# 4_1_frontend.net
KiCad netlist of a schematic drawn in Altium Designer
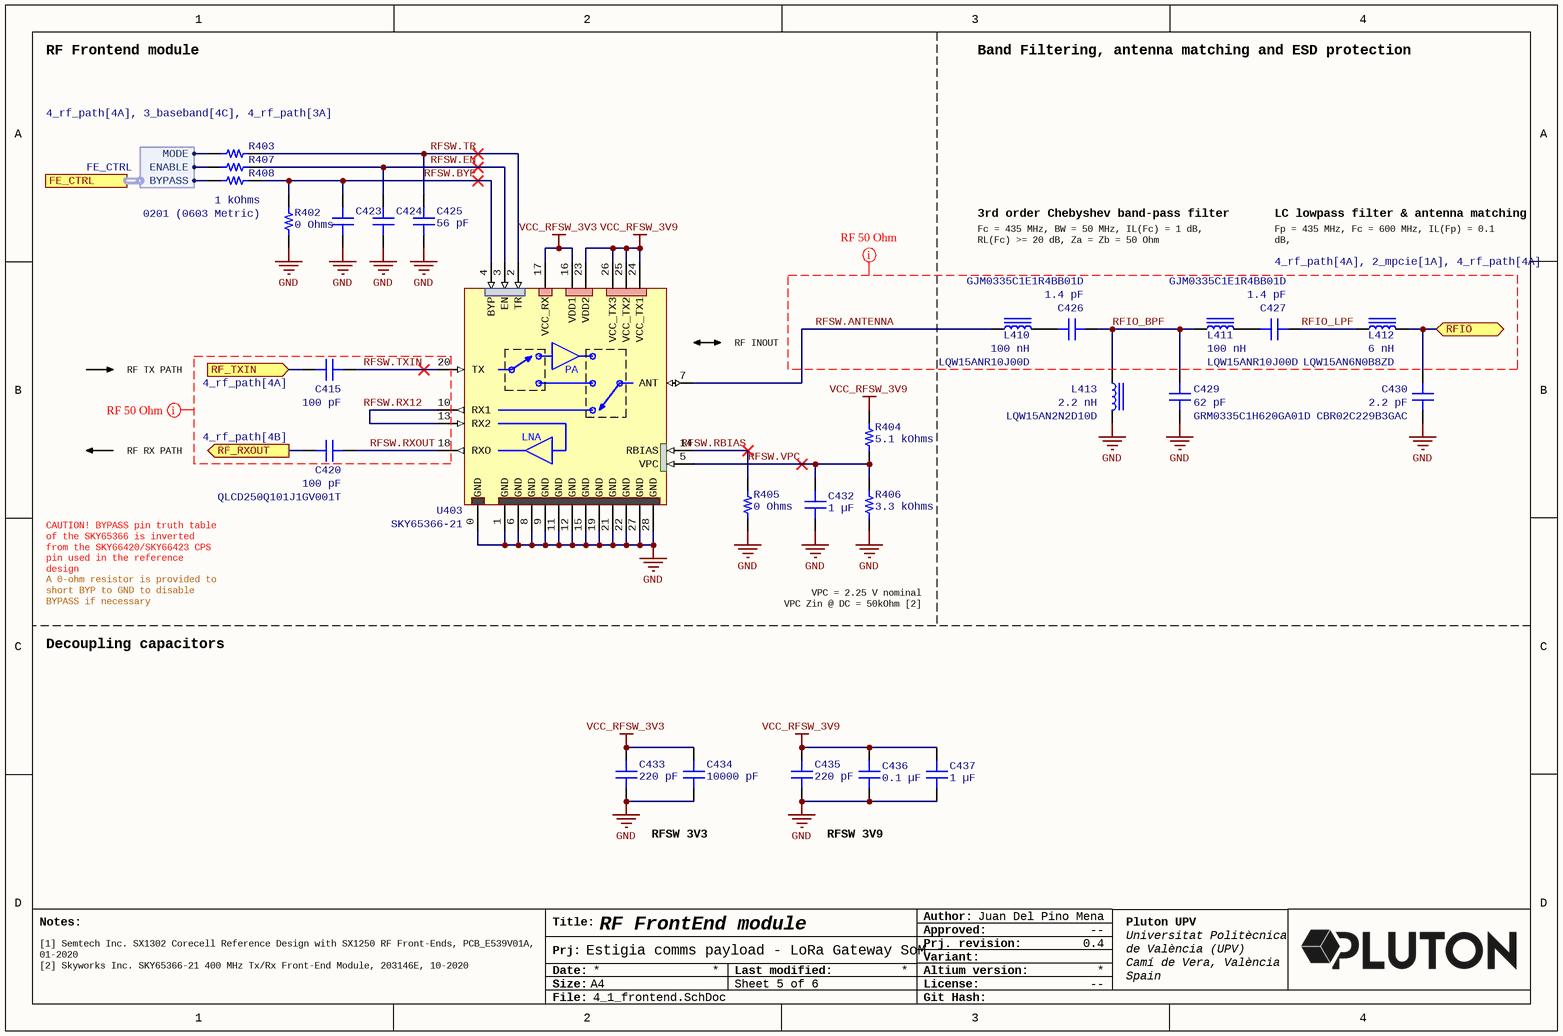
[diagram p0: 4_1_frontend.SchDoc]

(export (version "E")
  (design (tool "Eeschema 10.0.6"))
  (components
    (comp (ref "C415")
      (value "100 pF")
      (footprint "CAP 0201_0603 RF")
      (description "CAP CER 100PF 25V C0G/NP0 0201")
      (fields
        (field (name "PART NUMBER") "QLCD250Q101J1GV001T")
        (field (name "CAPACITANCE") "100 pF")
        (field (name "MANUFACTURER") "Johanson Technology Inc.")
        (field (name "TOLERANCE") "±5%")
      )
      (libsource (lib "Celestial Altium Library - altium_library") (part "Capacitor"))
    )
    (comp (ref "C420")
      (value "100 pF")
      (footprint "CAP 0201_0603 RF")
      (description "CAP CER 100PF 25V C0G/NP0 0201")
      (fields
        (field (name "PART NUMBER") "QLCD250Q101J1GV001T")
        (field (name "CAPACITANCE") "100 pF")
        (field (name "MANUFACTURER") "Johanson Technology Inc.")
      )
      (libsource (lib "Celestial Altium Library - altium_library") (part "Capacitor"))
    )
    (comp (ref "C423")
      (value "56 pF")
      (footprint "CAP 0201_0603")
      (description "CAP CER 56PF 50V C0G/NP0 0201")
      (fields
        (field (name "PART NUMBER") "GRM0335C1H560GA01D")
        (field (name "MANUFACTURER") "Murata Electronics")
      )
      (libsource (lib "Celestial Altium Library - altium_library") (part "Capacitor"))
    )
    (comp (ref "C424")
      (value "56 pF")
      (footprint "CAP 0201_0603")
      (description "CAP CER 56PF 50V C0G/NP0 0201")
      (fields
        (field (name "PART NUMBER") "GRM0335C1H560GA01D")
        (field (name "MANUFACTURER") "Murata Electronics")
      )
      (libsource (lib "Celestial Altium Library - altium_library") (part "Capacitor"))
    )
    (comp (ref "C425")
      (value "56 pF")
      (footprint "CAP 0201_0603")
      (description "CAP CER 56PF 50V C0G/NP0 0201")
      (fields
        (field (name "PART NUMBER") "GRM0335C1H560GA01D")
        (field (name "MANUFACTURER") "Murata Electronics")
      )
      (libsource (lib "Celestial Altium Library - altium_library") (part "Capacitor"))
    )
    (comp (ref "C426")
      (value "1.4 pF")
      (footprint "CAP 0201_0603 RF")
      (description "CAP CER 1.4PF 25V C0G/NP0 0201")
      (fields
        (field (name "PART NUMBER") "GJM0335C1E1R4BB01D")
        (field (name "MANUFACTURER") "Murata Electronics")
        (field (name "TOLERANCE") "±0.1pF")
      )
      (libsource (lib "Celestial Altium Library - altium_library") (part "Capacitor"))
    )
    (comp (ref "C427")
      (value "1.4 pF")
      (footprint "CAP 0201_0603 RF")
      (description "CAP CER 1.4PF 25V C0G/NP0 0201")
      (fields
        (field (name "PART NUMBER") "GJM0335C1E1R4BB01D")
        (field (name "MANUFACTURER") "Murata Electronics")
        (field (name "TOLERANCE") "±0.1pF")
      )
      (libsource (lib "Celestial Altium Library - altium_library") (part "Capacitor"))
    )
    (comp (ref "C429")
      (value "62 pF")
      (footprint "CAP 0201_0603")
      (description "CAP CER 62PF 50V C0G/NP0 0201")
      (fields
        (field (name "PART NUMBER") "GRM0335C1H620GA01D")
        (field (name "MANUFACTURER") "Murata Electronics")
        (field (name "TOLERANCE") "±2%")
      )
      (libsource (lib "Celestial Altium Library - altium_library") (part "Capacitor"))
    )
    (comp (ref "C430")
      (value "2.2 pF")
      (footprint "CAP 0201_0603 RF")
      (description "CAP CER 2.2PF 25V C0G/NP0 0201")
      (fields
        (field (name "PART NUMBER") "CBR02C229B3GAC")
        (field (name "MANUFACTURER") "KEMET")
        (field (name "TOLERANCE") "±0.1pF")
      )
      (libsource (lib "Celestial Altium Library - altium_library") (part "Capacitor"))
    )
    (comp (ref "C432")
      (value "1 µF")
      (footprint "CAP 0402_1005")
      (description "CAP CER 1UF 16V X5R 0402")
      (fields
        (field (name "PART NUMBER") "CL05A105KO5NNNC")
        (field (name "MANUFACTURER") "Samsung Electro-Mechanics")
      )
      (libsource (lib "Celestial Altium Library - altium_library") (part "Capacitor"))
    )
    (comp (ref "C433")
      (value "220 pF")
      (footprint "CAP 0201_0603")
      (description "CAP CER 220PF 50V C0G/NP0 0201")
      (fields
        (field (name "PART NUMBER") "GRM0335C1H221JA01D")
        (field (name "MANUFACTURER") "Murata Electronics")
      )
      (libsource (lib "Celestial Altium Library - altium_library") (part "Capacitor"))
    )
    (comp (ref "C434")
      (value "10000 pF")
      (footprint "CAP 0402_1005")
      (description "CAP CER 10000PF 25V C0G/NP0 0402")
      (fields
        (field (name "PART NUMBER") "GRM1555C1E103JE01J")
        (field (name "MANUFACTURER") "Murata Electronics")
      )
      (libsource (lib "Celestial Altium Library - altium_library") (part "Capacitor"))
    )
    (comp (ref "C435")
      (value "220 pF")
      (footprint "CAP 0201_0603")
      (description "CAP CER 220PF 50V C0G/NP0 0201")
      (fields
        (field (name "PART NUMBER") "GRM0335C1H221JA01D")
        (field (name "MANUFACTURER") "Murata Electronics")
      )
      (libsource (lib "Celestial Altium Library - altium_library") (part "Capacitor"))
    )
    (comp (ref "C436")
      (value "0.1 µF")
      (footprint "CAP 0402_1005")
      (description "CAP CER 0402 0.1UF 16V X7R 10%")
      (fields (field (name "PART NUMBER") "C0402C104K4RECAUTO") (field (name "MANUFACTURER") "KEMET"))
      (libsource (lib "Celestial Altium Library - altium_library") (part "Capacitor"))
    )
    (comp (ref "C437")
      (value "1 µF")
      (footprint "CAP 0402_1005")
      (description "CAP CER 1UF 10V X7S 0402")
      (fields
        (field (name "PART NUMBER") "GRT155C71A105KE13D")
        (field (name "MANUFACTURER") "Murata Electronics")
      )
      (libsource (lib "Celestial Altium Library - altium_library") (part "Capacitor"))
    )
    (comp (ref "L410")
      (value "100 nH")
      (footprint "IND 0402_1005 RF WW")
      (description "FIXED IND 100NH 120MA 2.52OHM SM")
      (fields
        (field (name "PART NUMBER") "LQW15ANR10J00D")
        (field (name "MANUFACTURER") "Murata Electronics")
        (field (name "TOLERANCE") "±5%")
      )
      (libsource (lib "Celestial Altium Library - altium_library") (part "Inductor"))
    )
    (comp (ref "L411")
      (value "100 nH")
      (footprint "IND 0402_1005 RF WW")
      (description "FIXED IND 100NH 120MA 2.52OHM SM")
      (fields
        (field (name "PART NUMBER") "LQW15ANR10J00D")
        (field (name "MANUFACTURER") "Murata Electronics")
        (field (name "TOLERANCE") "±5%")
      )
      (libsource (lib "Celestial Altium Library - altium_library") (part "Inductor"))
    )
    (comp (ref "L412")
      (value "6 nH")
      (footprint "IND 0402_1005 RF WW")
      (description "FIXED IND 6NH 1.6A 0.056OHM SMD")
      (fields
        (field (name "PART NUMBER") "LQW15AN6N0B8ZD")
        (field (name "MANUFACTURER") "Murata Electronics")
        (field (name "TOLERANCE") "±0.1nH")
      )
      (libsource (lib "Celestial Altium Library - altium_library") (part "Inductor"))
    )
    (comp (ref "L413")
      (value "2.2 nH")
      (footprint "IND 0402_1005 RF WW")
      (description "FIXED IND 2.2NH 1A 0.027OHM SMD")
      (fields
        (field (name "PART NUMBER") "LQW15AN2N2D10D")
        (field (name "MANUFACTURER") "Murata Electronics")
        (field (name "TOLERANCE") "±0.5nH")
      )
      (libsource (lib "Celestial Altium Library - altium_library") (part "Inductor"))
    )
    (comp (ref "R402")
      (value "0 Ohms")
      (footprint "RES 0201_0603")
      (description "RES SMD 0 OHM JUMPER 1/20W 0201")
      (fields (field (name "PART NUMBER") "AC0201JR-070RL") (field (name "MANUFACTURER") "Yageo"))
      (libsource (lib "Celestial Altium Library - altium_library") (part "Resistor"))
    )
    (comp (ref "R403")
      (value "1 kOhms")
      (footprint "RES 0201_0603")
      (description "RES 1K OHM 1% 1/20W 0201")
      (fields
        (field (name "PART NUMBER") "RC0201FR-071KL")
        (field (name "DEVICE PACKAGE") "0201 (0603 Metric)")
        (field (name "MANUFACTURER") "Yageo")
      )
      (libsource (lib "Celestial Altium Library - altium_library") (part "Resistor"))
    )
    (comp (ref "R404")
      (value "5.1 kOhms")
      (footprint "RES 0201_0603")
      (description "RES SMD 5.1K OHM 1% 1/20W 0201")
      (fields
        (field (name "PART NUMBER") "ERJ-1GNF5101C")
        (field (name "MANUFACTURER") "Panasonic Electronic Components")
      )
      (libsource (lib "Celestial Altium Library - altium_library") (part "Resistor"))
    )
    (comp (ref "R405")
      (value "0 Ohms")
      (footprint "RES 0201_0603")
      (description "RES SMD 0 OHM JUMPER 1/20W 0201")
      (fields (field (name "PART NUMBER") "AC0201JR-070RL") (field (name "MANUFACTURER") "Yageo"))
      (libsource (lib "Celestial Altium Library - altium_library") (part "Resistor"))
    )
    (comp (ref "R406")
      (value "3.3 kOhms")
      (footprint "RES 0201_0603")
      (description "RES SMD 3.3K OHM 1% 1/20W 0201")
      (fields
        (field (name "PART NUMBER") "ERJ-1GJF3301C")
        (field (name "MANUFACTURER") "Panasonic Electronic Components")
      )
      (libsource (lib "Celestial Altium Library - altium_library") (part "Resistor"))
    )
    (comp (ref "R407")
      (value "1 kOhms")
      (footprint "RES 0201_0603")
      (description "RES 1K OHM 1% 1/20W 0201")
      (fields (field (name "PART NUMBER") "RC0201FR-071KL") (field (name "MANUFACTURER") "Yageo"))
      (libsource (lib "Celestial Altium Library - altium_library") (part "Resistor"))
    )
    (comp (ref "R408")
      (value "1 kOhms")
      (footprint "RES 0201_0603")
      (description "RES 1K OHM 1% 1/20W 0201")
      (fields (field (name "PART NUMBER") "RC0201FR-071KL") (field (name "MANUFACTURER") "Yageo"))
      (libsource (lib "Celestial Altium Library - altium_library") (part "Resistor"))
    )
    (comp (ref "U403")
      (value "SKY65366-21")
      (footprint "MCM-28-SKY65366-21")
      (description "400 MHz Transmit/Receive Front-End Module")
      (libsource (lib "rf") (part "SKY65366-21"))
    )
  )
  (nets
    (net (code "2") (name "/BYPASS") (class "Default")
      (node (ref "R408") (pin "1") (pinfunction "1_1") (pintype "passive"))
    )
    (net (code "3") (name "/ENABLE") (class "Default")
      (node (ref "R407") (pin "1") (pinfunction "1_1") (pintype "passive"))
    )
    (net (code "4") (name "/MODE") (class "Default")
      (node (ref "R403") (pin "1") (pinfunction "1_1") (pintype "passive"))
    )
    (net (code "5") (name "/RFIO") (class "Default")
      (node (ref "C430") (pin "2") (pinfunction "2_2") (pintype "passive"))
      (node (ref "L412") (pin "2") (pinfunction "2_2") (pintype "passive"))
    )
    (net (code "6") (name "/RFIO_BPF") (class "Default")
      (node (ref "C426") (pin "2") (pinfunction "2_2") (pintype "passive"))
      (node (ref "C429") (pin "2") (pinfunction "2_2") (pintype "passive"))
      (node (ref "L411") (pin "1") (pinfunction "1_1") (pintype "passive"))
      (node (ref "L413") (pin "1") (pinfunction "1_1") (pintype "passive"))
    )
    (net (code "7") (name "/RFIO_LPF") (class "Default")
      (node (ref "C427") (pin "2") (pinfunction "2_2") (pintype "passive"))
      (node (ref "L412") (pin "1") (pinfunction "1_1") (pintype "passive"))
    )
    (net (code "8") (name "/RFSW.ANTENNA") (class "Default")
      (node (ref "L410") (pin "1") (pinfunction "1_1") (pintype "passive"))
      (node (ref "U403") (pin "7") (pinfunction "ANT_7") (pintype "bidirectional"))
    )
    (net (code "11") (name "/RFSW.BYP") (class "Default")
      (node (ref "C423") (pin "2") (pinfunction "2_2") (pintype "passive"))
      (node (ref "R402") (pin "2") (pinfunction "2_2") (pintype "passive"))
      (node (ref "R408") (pin "2") (pinfunction "2_2") (pintype "passive"))
      (node (ref "U403") (pin "4") (pinfunction "BYP_4") (pintype "input"))
    )
    (net (code "12") (name "/RFSW.EN") (class "Default")
      (node (ref "C424") (pin "2") (pinfunction "2_2") (pintype "passive"))
      (node (ref "R407") (pin "2") (pinfunction "2_2") (pintype "passive"))
      (node (ref "U403") (pin "3") (pinfunction "EN_3") (pintype "input"))
    )
    (net (code "13") (name "/RFSW.RBIAS") (class "Default")
      (node (ref "R405") (pin "2") (pinfunction "2_2") (pintype "passive"))
      (node (ref "U403") (pin "14") (pinfunction "RBIAS_14") (pintype "input"))
    )
    (net (code "17") (name "/RFSW.RX12") (class "Default")
      (node (ref "U403") (pin "10") (pinfunction "RX1_10") (pintype "output"))
      (node (ref "U403") (pin "13") (pinfunction "RX2_13") (pintype "input"))
    )
    (net (code "18") (name "/RFSW.RXOUT") (class "Default")
      (node (ref "C420") (pin "2") (pinfunction "2_2") (pintype "passive"))
      (node (ref "U403") (pin "18") (pinfunction "RXO_18") (pintype "output"))
    )
    (net (code "20") (name "/RFSW.TR") (class "Default")
      (node (ref "C425") (pin "2") (pinfunction "2_2") (pintype "passive"))
      (node (ref "R403") (pin "2") (pinfunction "2_2") (pintype "passive"))
      (node (ref "U403") (pin "2") (pinfunction "TR_2") (pintype "input"))
    )
    (net (code "21") (name "/RFSW.TXIN") (class "Default")
      (node (ref "C415") (pin "2") (pinfunction "2_2") (pintype "passive"))
      (node (ref "U403") (pin "20") (pinfunction "TX_20") (pintype "input"))
    )
    (net (code "22") (name "/RFSW.VPC") (class "Default")
      (node (ref "C432") (pin "2") (pinfunction "2_2") (pintype "passive"))
      (node (ref "R404") (pin "1") (pinfunction "1_1") (pintype "passive"))
      (node (ref "R406") (pin "2") (pinfunction "2_2") (pintype "passive"))
      (node (ref "U403") (pin "5") (pinfunction "VPC_5") (pintype "input"))
    )
    (net (code "23") (name "/RF_RXOUT") (class "Default")
      (node (ref "C420") (pin "1") (pinfunction "1_1") (pintype "passive"))
    )
    (net (code "24") (name "/RF_TXIN") (class "Default")
      (node (ref "C415") (pin "1") (pinfunction "1_1") (pintype "passive"))
    )
    (net (code "25") (name "GND") (class "Default")
      (node (ref "C423") (pin "1") (pinfunction "1_1") (pintype "passive"))
      (node (ref "C424") (pin "1") (pinfunction "1_1") (pintype "passive"))
      (node (ref "C425") (pin "1") (pinfunction "1_1") (pintype "passive"))
      (node (ref "C429") (pin "1") (pinfunction "1_1") (pintype "passive"))
      (node (ref "C430") (pin "1") (pinfunction "1_1") (pintype "passive"))
      (node (ref "C432") (pin "1") (pinfunction "1_1") (pintype "passive"))
      (node (ref "C433") (pin "1") (pinfunction "1_1") (pintype "passive"))
      (node (ref "C434") (pin "1") (pinfunction "1_1") (pintype "passive"))
      (node (ref "C435") (pin "1") (pinfunction "1_1") (pintype "passive"))
      (node (ref "C436") (pin "1") (pinfunction "1_1") (pintype "passive"))
      (node (ref "C437") (pin "1") (pinfunction "1_1") (pintype "passive"))
      (node (ref "L413") (pin "2") (pinfunction "2_2") (pintype "passive"))
      (node (ref "R402") (pin "1") (pinfunction "1_1") (pintype "passive"))
      (node (ref "R405") (pin "1") (pinfunction "1_1") (pintype "passive"))
      (node (ref "R406") (pin "1") (pinfunction "1_1") (pintype "passive"))
      (node (ref "U403") (pin "0") (pinfunction "GND_0") (pintype "power_in"))
      (node (ref "U403") (pin "1") (pinfunction "GND_1") (pintype "power_in"))
      (node (ref "U403") (pin "11") (pinfunction "GND_11") (pintype "power_in"))
      (node (ref "U403") (pin "12") (pinfunction "GND_12") (pintype "power_in"))
      (node (ref "U403") (pin "15") (pinfunction "GND_15") (pintype "power_in"))
      (node (ref "U403") (pin "19") (pinfunction "GND_19") (pintype "power_in"))
      (node (ref "U403") (pin "21") (pinfunction "GND_21") (pintype "power_in"))
      (node (ref "U403") (pin "22") (pinfunction "GND_22") (pintype "power_in"))
      (node (ref "U403") (pin "27") (pinfunction "GND_27") (pintype "power_in"))
      (node (ref "U403") (pin "28") (pinfunction "GND_28") (pintype "power_in"))
      (node (ref "U403") (pin "6") (pinfunction "GND_6") (pintype "power_in"))
      (node (ref "U403") (pin "8") (pinfunction "GND_8") (pintype "power_in"))
      (node (ref "U403") (pin "9") (pinfunction "GND_9") (pintype "power_in"))
    )
    (net (code "26") (name "Net-(C426-Pad1)") (class "Default")
      (node (ref "C426") (pin "1") (pinfunction "1_1") (pintype "passive"))
      (node (ref "L410") (pin "2") (pinfunction "2_2") (pintype "passive"))
    )
    (net (code "27") (name "Net-(C427-Pad1)") (class "Default")
      (node (ref "C427") (pin "1") (pinfunction "1_1") (pintype "passive"))
      (node (ref "L411") (pin "2") (pinfunction "2_2") (pintype "passive"))
    )
    (net (code "28") (name "VCC_RFSW_3V3") (class "Default")
      (node (ref "C433") (pin "2") (pinfunction "2_2") (pintype "passive"))
      (node (ref "C434") (pin "2") (pinfunction "2_2") (pintype "passive"))
      (node (ref "U403") (pin "16") (pinfunction "VDD1_16") (pintype "power_in"))
      (node (ref "U403") (pin "17") (pinfunction "VCC_RX_17") (pintype "power_in"))
    )
    (net (code "29") (name "VCC_RFSW_3V9") (class "Default")
      (node (ref "C435") (pin "2") (pinfunction "2_2") (pintype "passive"))
      (node (ref "C436") (pin "2") (pinfunction "2_2") (pintype "passive"))
      (node (ref "C437") (pin "2") (pinfunction "2_2") (pintype "passive"))
      (node (ref "R404") (pin "2") (pinfunction "2_2") (pintype "passive"))
      (node (ref "U403") (pin "23") (pinfunction "VDD2_23") (pintype "power_in"))
      (node (ref "U403") (pin "24") (pinfunction "VCC_TX1_24") (pintype "power_in"))
      (node (ref "U403") (pin "25") (pinfunction "VCC_TX2_25") (pintype "power_in"))
      (node (ref "U403") (pin "26") (pinfunction "VCC_TX3_26") (pintype "power_in"))
    )
  )
)
